# MotorControl.net
KiCad netlist of a schematic drawn in EAGLE
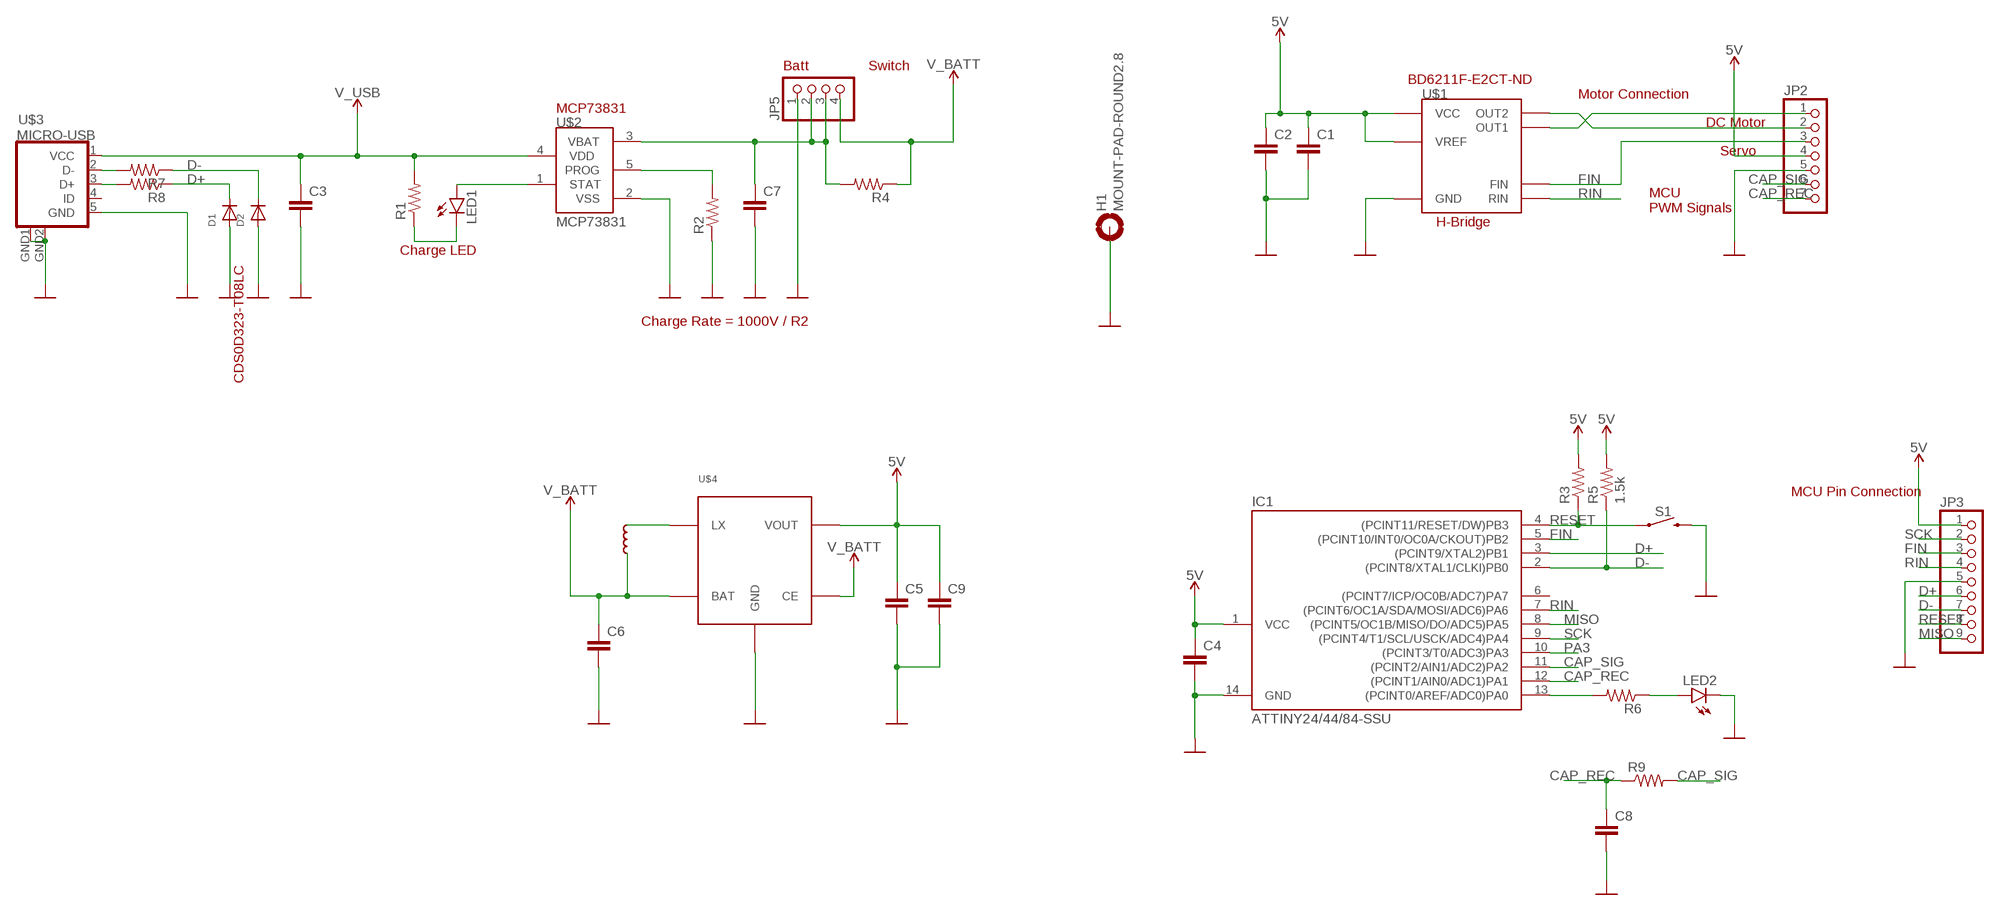
[diagram p0: schematic, sheet 1]

(export (version "E")
  (design (tool "Eeschema 10.0.6"))
  (components
    (comp (ref "C1")
      (value "C-EUC0603")
      (footprint "eagle-import:C0603")
      (libsource (lib "eagle-import") (part "C-EUC0603"))
    )
    (comp (ref "C2")
      (value "C-EUC0603")
      (footprint "eagle-import:C0603")
      (libsource (lib "eagle-import") (part "C-EUC0603"))
    )
    (comp (ref "C3")
      (value "C-EUC0603")
      (footprint "eagle-import:C0603")
      (libsource (lib "eagle-import") (part "C-EUC0603"))
    )
    (comp (ref "C4")
      (value "C-EUC0603")
      (footprint "eagle-import:C0603")
      (libsource (lib "eagle-import") (part "C-EUC0603"))
    )
    (comp (ref "C5")
      (value "C-EUC0603")
      (footprint "eagle-import:C0603")
      (libsource (lib "eagle-import") (part "C-EUC0603"))
    )
    (comp (ref "C6")
      (value "C-EUC0603")
      (footprint "eagle-import:C0603")
      (libsource (lib "eagle-import") (part "C-EUC0603"))
    )
    (comp (ref "C7")
      (value "C-EUC0603")
      (footprint "eagle-import:C0603")
      (libsource (lib "eagle-import") (part "C-EUC0603"))
    )
    (comp (ref "C8")
      (value "C-EUC0603")
      (footprint "eagle-import:C0603")
      (libsource (lib "eagle-import") (part "C-EUC0603"))
    )
    (comp (ref "C9")
      (value "C-EUC0603")
      (footprint "eagle-import:C0603")
      (libsource (lib "eagle-import") (part "C-EUC0603"))
    )
    (comp (ref "D1")
      (value "DIODESOD-323")
      (footprint "eagle-import:SOD-323")
      (libsource (lib "eagle-import") (part "DIODESOD-323"))
    )
    (comp (ref "D2")
      (value "DIODESOD-323")
      (footprint "eagle-import:SOD-323")
      (libsource (lib "eagle-import") (part "DIODESOD-323"))
    )
    (comp (ref "H1")
      (value "MOUNT-PAD-ROUND2.8")
      (footprint "eagle-import:2,8-PAD")
      (libsource (lib "eagle-import") (part "MOUNT-PAD-ROUND2.8"))
    )
    (comp (ref "IC1")
      (value "ATTINY24/44/84-SSU")
      (footprint "eagle-import:SOIC14")
      (libsource (lib "eagle-import") (part "ATTINY24/44/84-SSU"))
    )
    (comp (ref "JP2")
      (value "HEADER-1X7")
      (footprint "eagle-import:1X07_OVAL")
      (libsource (lib "eagle-import") (part "HEADER-1X7"))
    )
    (comp (ref "JP3")
      (value "HEADER-1X9")
      (footprint "eagle-import:1X09_OVAL")
      (libsource (lib "eagle-import") (part "HEADER-1X9"))
    )
    (comp (ref "JP5")
      (value "HEADER-1X4")
      (footprint "eagle-import:1X04_OVAL")
      (libsource (lib "eagle-import") (part "HEADER-1X4"))
    )
    (comp (ref "LED1")
      (value "LEDCHIP-LED0805")
      (footprint "eagle-import:CHIP-LED0805")
      (libsource (lib "eagle-import") (part "LEDCHIP-LED0805"))
    )
    (comp (ref "LED2")
      (value "LEDCHIP-LED0805")
      (footprint "eagle-import:CHIP-LED0805")
      (libsource (lib "eagle-import") (part "LEDCHIP-LED0805"))
    )
    (comp (ref "R1")
      (value "R-US_R0603")
      (footprint "eagle-import:R0603")
      (libsource (lib "eagle-import") (part "R-US_R0603"))
    )
    (comp (ref "R2")
      (value "R-US_R0603")
      (footprint "eagle-import:R0603")
      (libsource (lib "eagle-import") (part "R-US_R0603"))
    )
    (comp (ref "R3")
      (value "R-US_R0603")
      (footprint "eagle-import:R0603")
      (libsource (lib "eagle-import") (part "R-US_R0603"))
    )
    (comp (ref "R4")
      (value "R-US_R0603")
      (footprint "eagle-import:R0603")
      (libsource (lib "eagle-import") (part "R-US_R0603"))
    )
    (comp (ref "R5")
      (value "1.5k")
      (footprint "eagle-import:R0603")
      (libsource (lib "eagle-import") (part "R-US_R0603"))
    )
    (comp (ref "R6")
      (value "R-US_R0603")
      (footprint "eagle-import:R0603")
      (libsource (lib "eagle-import") (part "R-US_R0603"))
    )
    (comp (ref "R7")
      (value "R-US_R0603")
      (footprint "eagle-import:R0603")
      (libsource (lib "eagle-import") (part "R-US_R0603"))
    )
    (comp (ref "R8")
      (value "R-US_R0603")
      (footprint "eagle-import:R0603")
      (libsource (lib "eagle-import") (part "R-US_R0603"))
    )
    (comp (ref "R9")
      (value "R-US_R0603")
      (footprint "eagle-import:R0603")
      (libsource (lib "eagle-import") (part "R-US_R0603"))
    )
    (comp (ref "S1")
      (value "MOMENTARY-SWITCH-SPST-SMD-5.2MM")
      (footprint "eagle-import:TACTILE_SWITCH_SMD_5.2MM")
      (libsource (lib "eagle-import") (part "MOMENTARY-SWITCH-SPST-SMD-5.2MM"))
    )
    (comp (ref "U$1")
      (value "H-BRIDGE-BD6210F")
      (footprint "eagle-import:8-SOP")
      (libsource (lib "eagle-import") (part "H-BRIDGE-BD6210F"))
    )
    (comp (ref "U$2")
      (value "MCP73831")
      (footprint "eagle-import:SOT23-5L")
      (libsource (lib "eagle-import") (part "MCP73831"))
    )
    (comp (ref "U$3")
      (value "MICRO-USB")
      (footprint "eagle-import:MICRO-USB")
      (libsource (lib "eagle-import") (part "MICRO-USB"))
    )
    (comp (ref "U$4")
      (value "XC9141B50C")
      (footprint "eagle-import:SOT-25")
      (libsource (lib "eagle-import") (part "XC9141B50C"))
    )
    (comp (ref "U$5")
      (value "INDUCTOR")
      (footprint "eagle-import:SMD_INDUCTOR")
      (libsource (lib "eagle-import") (part "INDUCTOR"))
    )
  )
  (nets
    (net (code "1") (name "/CAP_REC") (class "Default")
      (node (ref "C8") (pin "1") (pinfunction "1_1") (pintype "passive"))
      (node (ref "IC1") (pin "12") (pinfunction "(PCINT1/AIN0/ADC1)PA1_12") (pintype "bidirectional"))
      (node (ref "JP2") (pin "7") (pinfunction "7_7") (pintype "passive"))
      (node (ref "R9") (pin "1") (pinfunction "1_1") (pintype "passive"))
    )
    (net (code "2") (name "/CAP_SIG") (class "Default")
      (node (ref "IC1") (pin "11") (pinfunction "(PCINT2/AIN1/ADC2)PA2_11") (pintype "bidirectional"))
      (node (ref "JP2") (pin "6") (pinfunction "6_6") (pintype "passive"))
      (node (ref "R9") (pin "2") (pinfunction "2_2") (pintype "passive"))
    )
    (net (code "3") (name "/D+") (class "Default")
      (node (ref "D1") (pin "C") (pinfunction "C_C") (pintype "passive"))
      (node (ref "IC1") (pin "3") (pinfunction "(PCINT9/XTAL2)PB1_3") (pintype "bidirectional"))
      (node (ref "JP3") (pin "6") (pinfunction "6_6") (pintype "passive"))
      (node (ref "R8") (pin "1") (pinfunction "1_1") (pintype "passive"))
    )
    (net (code "4") (name "/D-") (class "Default")
      (node (ref "D2") (pin "C") (pinfunction "C_C") (pintype "passive"))
      (node (ref "IC1") (pin "2") (pinfunction "(PCINT8/XTAL1/CLKI)PB0_2") (pintype "bidirectional"))
      (node (ref "JP3") (pin "7") (pinfunction "7_7") (pintype "passive"))
      (node (ref "R5") (pin "1") (pinfunction "1_1") (pintype "passive"))
      (node (ref "R7") (pin "1") (pinfunction "1_1") (pintype "passive"))
    )
    (net (code "5") (name "/FIN") (class "Default")
      (node (ref "IC1") (pin "5") (pinfunction "(PCINT10/INT0/OC0A/CKOUT)PB2_5") (pintype "bidirectional"))
      (node (ref "JP2") (pin "3") (pinfunction "3_3") (pintype "passive"))
      (node (ref "JP3") (pin "3") (pinfunction "3_3") (pintype "passive"))
      (node (ref "U$1") (pin "P$4") (pinfunction "FIN_P$4") (pintype "bidirectional"))
    )
    (net (code "6") (name "/MISO") (class "Default")
      (node (ref "IC1") (pin "8") (pinfunction "(PCINT5/OC1B/MISO/DO/ADC5)PA5_8") (pintype "bidirectional"))
      (node (ref "JP3") (pin "9") (pinfunction "9_9") (pintype "passive"))
    )
    (net (code "7") (name "/PA3") (class "Default")
      (node (ref "IC1") (pin "10") (pinfunction "(PCINT3/T0/ADC3)PA3_10") (pintype "bidirectional"))
    )
    (net (code "8") (name "/RESET") (class "Default")
      (node (ref "IC1") (pin "4") (pinfunction "(PCINT11/RESET/DW)PB3_4") (pintype "bidirectional"))
      (node (ref "JP3") (pin "8") (pinfunction "8_8") (pintype "passive"))
      (node (ref "R3") (pin "1") (pinfunction "1_1") (pintype "passive"))
      (node (ref "S1") (pin "1") (pinfunction "1_1") (pintype "passive"))
    )
    (net (code "9") (name "/RIN") (class "Default")
      (node (ref "IC1") (pin "7") (pinfunction "(PCINT6/OC1A/SDA/MOSI/ADC6)PA6_7") (pintype "bidirectional"))
      (node (ref "JP3") (pin "4") (pinfunction "4_4") (pintype "passive"))
      (node (ref "U$1") (pin "P$5") (pinfunction "RIN_P$5") (pintype "bidirectional"))
    )
    (net (code "10") (name "/SCK") (class "Default")
      (node (ref "IC1") (pin "9") (pinfunction "(PCINT4/T1/SCL/USCK/ADC4)PA4_9") (pintype "bidirectional"))
      (node (ref "JP3") (pin "2") (pinfunction "2_2") (pintype "passive"))
    )
    (net (code "11") (name "5V") (class "Default")
      (node (ref "C1") (pin "1") (pinfunction "1_1") (pintype "passive"))
      (node (ref "C2") (pin "1") (pinfunction "1_1") (pintype "passive"))
      (node (ref "C4") (pin "1") (pinfunction "1_1") (pintype "passive"))
      (node (ref "C5") (pin "1") (pinfunction "1_1") (pintype "passive"))
      (node (ref "C9") (pin "1") (pinfunction "1_1") (pintype "passive"))
      (node (ref "IC1") (pin "1") (pinfunction "VCC_1") (pintype "power_in"))
      (node (ref "JP2") (pin "4") (pinfunction "4_4") (pintype "passive"))
      (node (ref "JP3") (pin "1") (pinfunction "1_1") (pintype "passive"))
      (node (ref "R3") (pin "2") (pinfunction "2_2") (pintype "passive"))
      (node (ref "R5") (pin "2") (pinfunction "2_2") (pintype "passive"))
      (node (ref "U$1") (pin "P$2") (pinfunction "VCC_P$2") (pintype "bidirectional"))
      (node (ref "U$1") (pin "P$3") (pinfunction "VCC_P$3") (pintype "bidirectional"))
      (node (ref "U$1") (pin "P$6") (pinfunction "VREF_P$6") (pintype "bidirectional"))
      (node (ref "U$4") (pin "P$4") (pinfunction "VOUT_P$4") (pintype "bidirectional"))
    )
    (net (code "12") (name "GND") (class "Default")
      (node (ref "C1") (pin "2") (pinfunction "2_2") (pintype "passive"))
      (node (ref "C2") (pin "2") (pinfunction "2_2") (pintype "passive"))
      (node (ref "C3") (pin "2") (pinfunction "2_2") (pintype "passive"))
      (node (ref "C4") (pin "2") (pinfunction "2_2") (pintype "passive"))
      (node (ref "C5") (pin "2") (pinfunction "2_2") (pintype "passive"))
      (node (ref "C6") (pin "2") (pinfunction "2_2") (pintype "passive"))
      (node (ref "C7") (pin "2") (pinfunction "2_2") (pintype "passive"))
      (node (ref "C8") (pin "2") (pinfunction "2_2") (pintype "passive"))
      (node (ref "C9") (pin "2") (pinfunction "2_2") (pintype "passive"))
      (node (ref "D1") (pin "A") (pinfunction "A_A") (pintype "passive"))
      (node (ref "D2") (pin "A") (pinfunction "A_A") (pintype "passive"))
      (node (ref "H1") (pin "B2,8") (pinfunction "MOUNT_B2,8") (pintype "passive"))
      (node (ref "IC1") (pin "14") (pinfunction "GND_14") (pintype "power_in"))
      (node (ref "JP2") (pin "5") (pinfunction "5_5") (pintype "passive"))
      (node (ref "JP3") (pin "5") (pinfunction "5_5") (pintype "passive"))
      (node (ref "JP5") (pin "1") (pinfunction "1_1") (pintype "passive"))
      (node (ref "LED2") (pin "C") (pinfunction "C_C") (pintype "passive"))
      (node (ref "R2") (pin "1") (pinfunction "1_1") (pintype "passive"))
      (node (ref "S1") (pin "3") (pinfunction "2_3") (pintype "passive"))
      (node (ref "U$1") (pin "P$8") (pinfunction "GND_P$8") (pintype "bidirectional"))
      (node (ref "U$2") (pin "2") (pinfunction "VSS_2") (pintype "bidirectional"))
      (node (ref "U$3") (pin "5") (pinfunction "GND_5") (pintype "power_in"))
      (node (ref "U$3") (pin "GND1") (pinfunction "GND_GND1") (pintype "power_in"))
      (node (ref "U$3") (pin "GND2") (pinfunction "GND_GND2") (pintype "power_in"))
      (node (ref "U$4") (pin "P$2") (pinfunction "GND_P$2") (pintype "bidirectional"))
    )
    (net (code "13") (name "Net-(IC1-(PCINT0{slash}AREF{slash}ADC0)PA0)") (class "Default")
      (node (ref "IC1") (pin "13") (pinfunction "(PCINT0/AREF/ADC0)PA0_13") (pintype "bidirectional"))
      (node (ref "R6") (pin "2") (pinfunction "2_2") (pintype "passive"))
    )
    (net (code "14") (name "Net-(LED1-PadC)") (class "Default")
      (node (ref "LED1") (pin "C") (pinfunction "C_C") (pintype "passive"))
      (node (ref "R1") (pin "1") (pinfunction "1_1") (pintype "passive"))
    )
    (net (code "15") (name "Net-(LED2-PadA)") (class "Default")
      (node (ref "LED2") (pin "A") (pinfunction "A_A") (pintype "passive"))
      (node (ref "R6") (pin "1") (pinfunction "1_1") (pintype "passive"))
    )
    (net (code "16") (name "Net-(U$1-OUT1)") (class "Default")
      (node (ref "JP2") (pin "1") (pinfunction "1_1") (pintype "passive"))
      (node (ref "U$1") (pin "P$1") (pinfunction "OUT1_P$1") (pintype "bidirectional"))
    )
    (net (code "17") (name "Net-(U$1-OUT2)") (class "Default")
      (node (ref "JP2") (pin "2") (pinfunction "2_2") (pintype "passive"))
      (node (ref "U$1") (pin "P$7") (pinfunction "OUT2_P$7") (pintype "bidirectional"))
    )
    (net (code "18") (name "Net-(U$2-PROG)") (class "Default")
      (node (ref "R2") (pin "2") (pinfunction "2_2") (pintype "passive"))
      (node (ref "U$2") (pin "5") (pinfunction "PROG_5") (pintype "bidirectional"))
    )
    (net (code "19") (name "Net-(U$2-STAT)") (class "Default")
      (node (ref "LED1") (pin "A") (pinfunction "A_A") (pintype "passive"))
      (node (ref "U$2") (pin "1") (pinfunction "STAT_1") (pintype "bidirectional"))
    )
    (net (code "20") (name "Net-(U$2-VBAT)") (class "Default")
      (node (ref "C7") (pin "1") (pinfunction "1_1") (pintype "passive"))
      (node (ref "JP5") (pin "2") (pinfunction "2_2") (pintype "passive"))
      (node (ref "JP5") (pin "3") (pinfunction "3_3") (pintype "passive"))
      (node (ref "R4") (pin "2") (pinfunction "2_2") (pintype "passive"))
      (node (ref "U$2") (pin "3") (pinfunction "VBAT_3") (pintype "bidirectional"))
    )
    (net (code "21") (name "Net-(U$3-D+)") (class "Default")
      (node (ref "R8") (pin "2") (pinfunction "2_2") (pintype "passive"))
      (node (ref "U$3") (pin "3") (pinfunction "D+_3") (pintype "bidirectional"))
    )
    (net (code "22") (name "Net-(U$3-D-)") (class "Default")
      (node (ref "R7") (pin "2") (pinfunction "2_2") (pintype "passive"))
      (node (ref "U$3") (pin "2") (pinfunction "D-_2") (pintype "bidirectional"))
    )
    (net (code "23") (name "Net-(U$4-LX)") (class "Default")
      (node (ref "U$4") (pin "P$5") (pinfunction "LX_P$5") (pintype "bidirectional"))
      (node (ref "U$5") (pin "P$2") (pinfunction "P$2_P$2") (pintype "bidirectional"))
    )
    (net (code "24") (name "V_BATT") (class "Default")
      (node (ref "C6") (pin "1") (pinfunction "1_1") (pintype "passive"))
      (node (ref "JP5") (pin "4") (pinfunction "4_4") (pintype "passive"))
      (node (ref "R4") (pin "1") (pinfunction "1_1") (pintype "passive"))
      (node (ref "U$4") (pin "P$1") (pinfunction "CE_P$1") (pintype "bidirectional"))
      (node (ref "U$4") (pin "P$3") (pinfunction "BAT_P$3") (pintype "bidirectional"))
      (node (ref "U$5") (pin "P$1") (pinfunction "P$1_P$1") (pintype "bidirectional"))
    )
    (net (code "25") (name "V_USB") (class "Default")
      (node (ref "C3") (pin "1") (pinfunction "1_1") (pintype "passive"))
      (node (ref "R1") (pin "2") (pinfunction "2_2") (pintype "passive"))
      (node (ref "U$2") (pin "4") (pinfunction "VDD_4") (pintype "bidirectional"))
      (node (ref "U$3") (pin "1") (pinfunction "VCC_1") (pintype "power_in"))
    )
    (net (code "26") (name "unconnected-(IC1-(PCINT7{slash}ICP{slash}OC0B{slash}ADC7)PA7-Pad6)") (class "Default")
      (node (ref "IC1") (pin "6") (pinfunction "(PCINT7/ICP/OC0B/ADC7)PA7_6") (pintype "bidirectional"))
    )
    (net (code "27") (name "unconnected-(U$3-ID-Pad4)") (class "Default")
      (node (ref "U$3") (pin "4") (pinfunction "ID_4") (pintype "bidirectional"))
    )
  )
)
